# Solar_FeatherWing_02.net
KiCad netlist of a schematic drawn in EAGLE
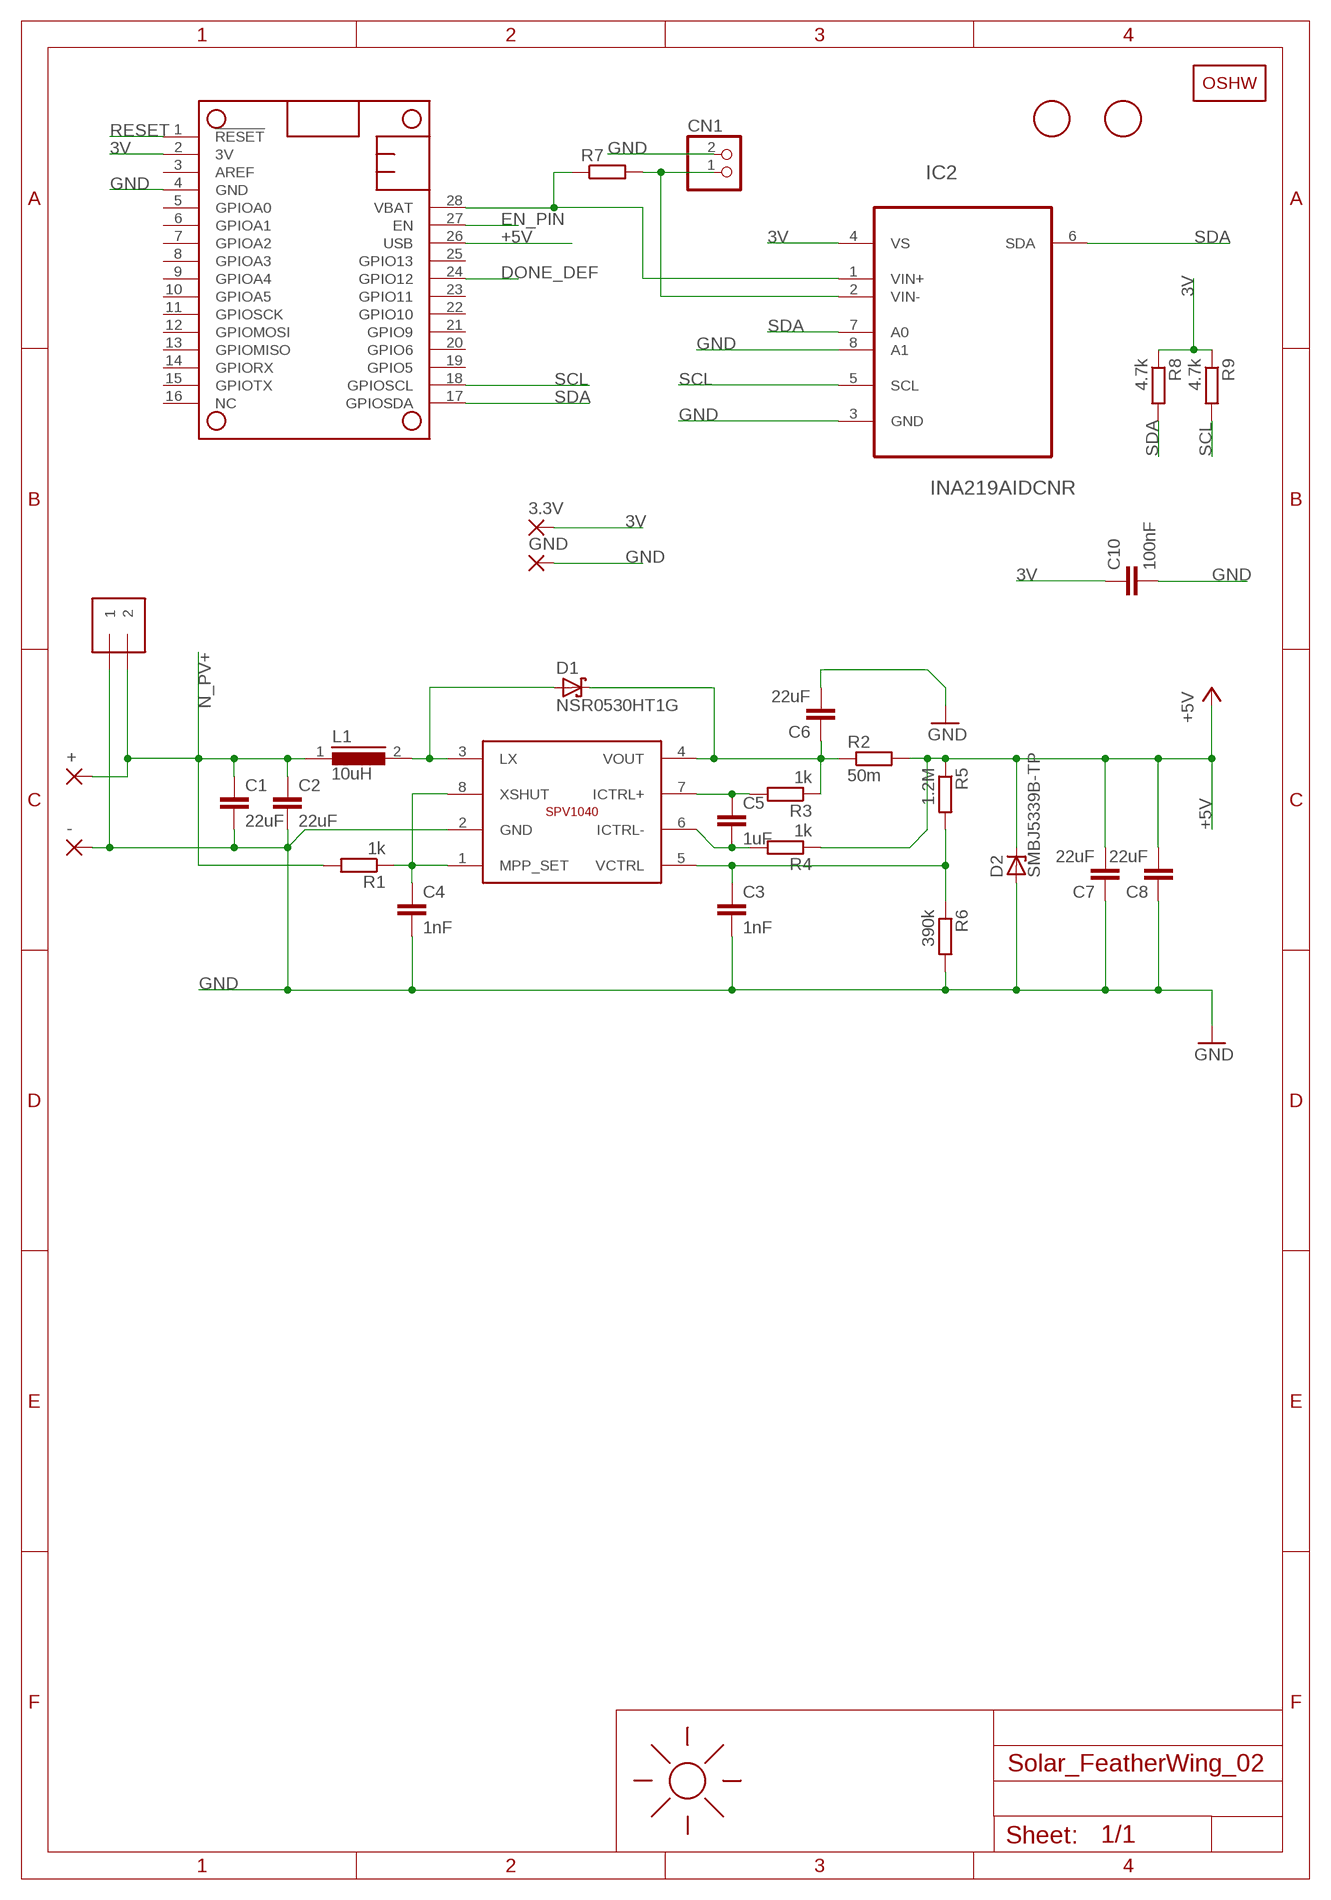
[diagram p0: schematic, sheet 1]

(export (version "E")
  (design (tool "Eeschema 10.0.6"))
  (components
    (comp (ref "+")
      (value "1,6/0,9")
      (footprint "eagle-import:1,6_0,9")
      (libsource (lib "eagle-import") (part "1,6/0,9"))
    )
    (comp (ref "-")
      (value "1,6/0,9")
      (footprint "eagle-import:1,6_0,9")
      (libsource (lib "eagle-import") (part "1,6/0,9"))
    )
    (comp (ref "3.3V")
      (value "1,6/0,9")
      (footprint "eagle-import:1,6_0,9")
      (libsource (lib "eagle-import") (part "1,6/0,9"))
    )
    (comp (ref "C1")
      (value "22uF")
      (footprint "eagle-import:C0603K")
      (libsource (lib "eagle-import") (part "C-EUC0603K"))
    )
    (comp (ref "C2")
      (value "22uF")
      (footprint "eagle-import:C0603K")
      (libsource (lib "eagle-import") (part "C-EUC0603K"))
    )
    (comp (ref "C3")
      (value "1nF")
      (footprint "eagle-import:C0603K")
      (libsource (lib "eagle-import") (part "C-EUC0603K"))
    )
    (comp (ref "C4")
      (value "1nF")
      (footprint "eagle-import:C0603K")
      (libsource (lib "eagle-import") (part "C-EUC0603K"))
    )
    (comp (ref "C5")
      (value "1uF")
      (footprint "eagle-import:C0603K")
      (libsource (lib "eagle-import") (part "C-EUC0603K"))
    )
    (comp (ref "C6")
      (value "22uF")
      (footprint "eagle-import:C0603K")
      (libsource (lib "eagle-import") (part "C-EUC0603K"))
    )
    (comp (ref "C7")
      (value "22uF")
      (footprint "eagle-import:C0603K")
      (libsource (lib "eagle-import") (part "C-EUC0603K"))
    )
    (comp (ref "C8")
      (value "22uF")
      (footprint "eagle-import:C0603K")
      (libsource (lib "eagle-import") (part "C-EUC0603K"))
    )
    (comp (ref "C10")
      (value "100nF")
      (footprint "eagle-import:C0603K")
      (libsource (lib "eagle-import") (part "C-EUC0603K"))
    )
    (comp (ref "CN1")
      (value "JST_2PIN-SMT-RA")
      (footprint "eagle-import:JST-PH-2-SMT-RA")
      (libsource (lib "eagle-import") (part "JST_2PIN-SMT-RA"))
    )
    (comp (ref "D1")
      (value "NSR0530HT1G")
      (footprint "eagle-import:SOD323_ST")
      (libsource (lib "eagle-import") (part "BAT60J"))
    )
    (comp (ref "D2")
      (value "SMBJ5339B-TP")
      (footprint "eagle-import:SMB")
      (libsource (lib "eagle-import") (part "ZENER-DIODESMB"))
    )
    (comp (ref "GND")
      (value "1,6/0,9")
      (footprint "eagle-import:1,6_0,9")
      (libsource (lib "eagle-import") (part "1,6/0,9"))
    )
    (comp (ref "IC1")
      (value "SPV1040T")
      (footprint "eagle-import:TSSOP8")
      (libsource (lib "eagle-import") (part "SPV1040T"))
    )
    (comp (ref "IC2")
      (value "INA219AIDCNR")
      (footprint "eagle-import:SOT65P280X145-8N")
      (libsource (lib "eagle-import") (part "INA219AIDCNR"))
    )
    (comp (ref "J1")
      (value "1X2-3.5MM")
      (footprint "eagle-import:1X2-3.5MM")
      (libsource (lib "eagle-import") (part "1X2-3.5MM"))
    )
    (comp (ref "L1")
      (value "10uH")
      (footprint "eagle-import:DR74")
      (libsource (lib "eagle-import") (part "DR74"))
    )
    (comp (ref "LOGO1")
      (value "OSHW_LOGOX0100")
      (footprint "eagle-import:OSHW_6X100")
      (libsource (lib "eagle-import") (part "OSHW_LOGOX0100"))
    )
    (comp (ref "MS1")
      (value "FEATHERWING")
      (footprint "eagle-import:FEATHERWING")
      (libsource (lib "eagle-import") (part "FEATHERWING"))
    )
    (comp (ref "R1")
      (value "1k")
      (footprint "eagle-import:R0603")
      (libsource (lib "eagle-import") (part "R-EU_R0603"))
    )
    (comp (ref "R2")
      (value "50m")
      (footprint "eagle-import:R0603")
      (libsource (lib "eagle-import") (part "R-EU_R0603"))
    )
    (comp (ref "R3")
      (value "1k")
      (footprint "eagle-import:R0603")
      (libsource (lib "eagle-import") (part "R-EU_R0603"))
    )
    (comp (ref "R4")
      (value "1k")
      (footprint "eagle-import:R0603")
      (libsource (lib "eagle-import") (part "R-EU_R0603"))
    )
    (comp (ref "R5")
      (value "1.2M")
      (footprint "eagle-import:R0603")
      (libsource (lib "eagle-import") (part "R-EU_R0603"))
    )
    (comp (ref "R6")
      (value "390k")
      (footprint "eagle-import:R0603")
      (libsource (lib "eagle-import") (part "R-EU_R0603"))
    )
    (comp (ref "R7")
      (value "R-EU_R1206")
      (footprint "eagle-import:R1206")
      (libsource (lib "eagle-import") (part "R-EU_R1206"))
    )
    (comp (ref "R8")
      (value "4.7k")
      (footprint "eagle-import:R0603")
      (libsource (lib "eagle-import") (part "R-EU_R0603"))
    )
    (comp (ref "R9")
      (value "4.7k")
      (footprint "eagle-import:R0603")
      (libsource (lib "eagle-import") (part "R-EU_R0603"))
    )
    (comp (ref "U$1")
      (value "SUNLOGO")
      (footprint "eagle-import:SUN")
      (libsource (lib "eagle-import") (part "SUNLOGO"))
    )
    (comp (ref "U$2")
      (value "FIDUCIAL")
      (footprint "eagle-import:FIDUCIAL_1MM")
      (libsource (lib "eagle-import") (part "FIDUCIAL"))
    )
    (comp (ref "U$3")
      (value "FIDUCIAL")
      (footprint "eagle-import:FIDUCIAL_1MM")
      (libsource (lib "eagle-import") (part "FIDUCIAL"))
    )
  )
  (nets
    (net (code "1") (name "+5V") (class "Default")
      (node (ref "C7") (pin "2") (pinfunction "2_2") (pintype "passive"))
      (node (ref "C8") (pin "2") (pinfunction "2_2") (pintype "passive"))
      (node (ref "D2") (pin "C") (pinfunction "C_C") (pintype "passive"))
      (node (ref "MS1") (pin "26") (pinfunction "USB_26") (pintype "power_in"))
      (node (ref "R2") (pin "2") (pinfunction "2_2") (pintype "passive"))
      (node (ref "R4") (pin "1") (pinfunction "1_1") (pintype "passive"))
      (node (ref "R5") (pin "1") (pinfunction "1_1") (pintype "passive"))
    )
    (net (code "2") (name "/3V") (class "Default")
      (node (ref "3.3V") (pin "1") (pinfunction "P_1") (pintype "passive"))
      (node (ref "C10") (pin "1") (pinfunction "1_1") (pintype "passive"))
      (node (ref "IC2") (pin "4") (pinfunction "VS_4") (pintype "power_in"))
      (node (ref "MS1") (pin "2") (pinfunction "3V_2") (pintype "power_in"))
      (node (ref "R8") (pin "1") (pinfunction "1_1") (pintype "passive"))
      (node (ref "R9") (pin "1") (pinfunction "1_1") (pintype "passive"))
    )
    (net (code "3") (name "/DONE_DEF") (class "Default")
      (node (ref "MS1") (pin "24") (pinfunction "GPIO12_24") (pintype "bidirectional"))
    )
    (net (code "4") (name "/EN_PIN") (class "Default")
      (node (ref "MS1") (pin "27") (pinfunction "EN_27") (pintype "passive"))
    )
    (net (code "5") (name "/N_PV+") (class "Default")
      (node (ref "+") (pin "1") (pinfunction "P_1") (pintype "passive"))
      (node (ref "C1") (pin "1") (pinfunction "1_1") (pintype "passive"))
      (node (ref "C2") (pin "1") (pinfunction "1_1") (pintype "passive"))
      (node (ref "J1") (pin "2") (pinfunction "2_2") (pintype "passive"))
      (node (ref "L1") (pin "1") (pinfunction "1_1") (pintype "passive"))
      (node (ref "R1") (pin "2") (pinfunction "2_2") (pintype "passive"))
    )
    (net (code "6") (name "/RESET") (class "Default")
      (node (ref "MS1") (pin "1") (pinfunction "~{RESET}_1") (pintype "input"))
    )
    (net (code "7") (name "/SCL") (class "Default")
      (node (ref "IC2") (pin "5") (pinfunction "SCL_5") (pintype "input"))
      (node (ref "MS1") (pin "18") (pinfunction "GPIOSCL_18") (pintype "bidirectional"))
      (node (ref "R9") (pin "2") (pinfunction "2_2") (pintype "passive"))
    )
    (net (code "8") (name "/SDA") (class "Default")
      (node (ref "IC2") (pin "6") (pinfunction "SDA_6") (pintype "bidirectional"))
      (node (ref "IC2") (pin "7") (pinfunction "A0_7") (pintype "input"))
      (node (ref "MS1") (pin "17") (pinfunction "GPIOSDA_17") (pintype "bidirectional"))
      (node (ref "R8") (pin "2") (pinfunction "2_2") (pintype "passive"))
    )
    (net (code "9") (name "GND") (class "Default")
      (node (ref "-") (pin "1") (pinfunction "P_1") (pintype "passive"))
      (node (ref "C1") (pin "2") (pinfunction "2_2") (pintype "passive"))
      (node (ref "C10") (pin "2") (pinfunction "2_2") (pintype "passive"))
      (node (ref "C2") (pin "2") (pinfunction "2_2") (pintype "passive"))
      (node (ref "C3") (pin "2") (pinfunction "2_2") (pintype "passive"))
      (node (ref "C4") (pin "2") (pinfunction "2_2") (pintype "passive"))
      (node (ref "C6") (pin "2") (pinfunction "2_2") (pintype "passive"))
      (node (ref "C7") (pin "1") (pinfunction "1_1") (pintype "passive"))
      (node (ref "C8") (pin "1") (pinfunction "1_1") (pintype "passive"))
      (node (ref "CN1") (pin "2") (pinfunction "1_2") (pintype "passive"))
      (node (ref "D2") (pin "A") (pinfunction "A_A") (pintype "passive"))
      (node (ref "GND") (pin "1") (pinfunction "P_1") (pintype "passive"))
      (node (ref "IC1") (pin "2") (pinfunction "GND_2") (pintype "power_in"))
      (node (ref "IC2") (pin "3") (pinfunction "GND_3") (pintype "passive"))
      (node (ref "IC2") (pin "8") (pinfunction "A1_8") (pintype "input"))
      (node (ref "J1") (pin "1") (pinfunction "1_1") (pintype "passive"))
      (node (ref "MS1") (pin "4") (pinfunction "GND_4") (pintype "power_in"))
      (node (ref "R6") (pin "2") (pinfunction "2_2") (pintype "passive"))
    )
    (net (code "10") (name "Net-(CN1-2)") (class "Default")
      (node (ref "CN1") (pin "1") (pinfunction "2_1") (pintype "passive"))
      (node (ref "IC2") (pin "2") (pinfunction "VIN-_2") (pintype "input"))
      (node (ref "R7") (pin "2") (pinfunction "2_2") (pintype "passive"))
    )
    (net (code "11") (name "Net-(IC1-ICTRL+)") (class "Default")
      (node (ref "C5") (pin "1") (pinfunction "1_1") (pintype "passive"))
      (node (ref "IC1") (pin "7") (pinfunction "ICTRL+_7") (pintype "input"))
      (node (ref "R3") (pin "2") (pinfunction "2_2") (pintype "passive"))
    )
    (net (code "12") (name "Net-(IC1-ICTRL-)") (class "Default")
      (node (ref "C5") (pin "2") (pinfunction "2_2") (pintype "passive"))
      (node (ref "IC1") (pin "6") (pinfunction "ICTRL-_6") (pintype "input"))
      (node (ref "R4") (pin "2") (pinfunction "2_2") (pintype "passive"))
    )
    (net (code "13") (name "Net-(IC1-LX)") (class "Default")
      (node (ref "D1") (pin "A") (pinfunction "A_A") (pintype "passive"))
      (node (ref "IC1") (pin "3") (pinfunction "LX_3") (pintype "power_in"))
      (node (ref "L1") (pin "2") (pinfunction "2_2") (pintype "passive"))
    )
    (net (code "14") (name "Net-(IC1-MPP_SET)") (class "Default")
      (node (ref "C4") (pin "1") (pinfunction "1_1") (pintype "passive"))
      (node (ref "IC1") (pin "1") (pinfunction "MPP_SET_1") (pintype "input"))
      (node (ref "IC1") (pin "8") (pinfunction "XSHUT_8") (pintype "input"))
      (node (ref "R1") (pin "1") (pinfunction "1_1") (pintype "passive"))
    )
    (net (code "15") (name "Net-(IC1-VCTRL)") (class "Default")
      (node (ref "C3") (pin "1") (pinfunction "1_1") (pintype "passive"))
      (node (ref "IC1") (pin "5") (pinfunction "VCTRL_5") (pintype "input"))
      (node (ref "R5") (pin "2") (pinfunction "2_2") (pintype "passive"))
      (node (ref "R6") (pin "1") (pinfunction "1_1") (pintype "passive"))
    )
    (net (code "16") (name "Net-(IC1-VOUT)") (class "Default")
      (node (ref "C6") (pin "1") (pinfunction "1_1") (pintype "passive"))
      (node (ref "D1") (pin "C") (pinfunction "C_C") (pintype "passive"))
      (node (ref "IC1") (pin "4") (pinfunction "VOUT_4") (pintype "power_in"))
      (node (ref "R2") (pin "1") (pinfunction "1_1") (pintype "passive"))
      (node (ref "R3") (pin "1") (pinfunction "1_1") (pintype "passive"))
    )
    (net (code "17") (name "Net-(IC2-VIN+)") (class "Default")
      (node (ref "IC2") (pin "1") (pinfunction "VIN+_1") (pintype "input"))
      (node (ref "MS1") (pin "28") (pinfunction "VBAT_28") (pintype "power_in"))
      (node (ref "R7") (pin "1") (pinfunction "1_1") (pintype "passive"))
    )
    (net (code "18") (name "unconnected-(MS1-AREF-Pad3)") (class "Default")
      (node (ref "MS1") (pin "3") (pinfunction "AREF_3") (pintype "passive"))
    )
    (net (code "19") (name "unconnected-(MS1-GPIO5-Pad19)") (class "Default")
      (node (ref "MS1") (pin "19") (pinfunction "GPIO5_19") (pintype "bidirectional"))
    )
    (net (code "20") (name "unconnected-(MS1-GPIO6-Pad20)") (class "Default")
      (node (ref "MS1") (pin "20") (pinfunction "GPIO6_20") (pintype "bidirectional"))
    )
    (net (code "21") (name "unconnected-(MS1-GPIO9-Pad21)") (class "Default")
      (node (ref "MS1") (pin "21") (pinfunction "GPIO9_21") (pintype "bidirectional"))
    )
    (net (code "22") (name "unconnected-(MS1-GPIO10-Pad22)") (class "Default")
      (node (ref "MS1") (pin "22") (pinfunction "GPIO10_22") (pintype "bidirectional"))
    )
    (net (code "23") (name "unconnected-(MS1-GPIO11-Pad23)") (class "Default")
      (node (ref "MS1") (pin "23") (pinfunction "GPIO11_23") (pintype "bidirectional"))
    )
    (net (code "24") (name "unconnected-(MS1-GPIO13-Pad25)") (class "Default")
      (node (ref "MS1") (pin "25") (pinfunction "GPIO13_25") (pintype "bidirectional"))
    )
    (net (code "25") (name "unconnected-(MS1-GPIOA0-Pad5)") (class "Default")
      (node (ref "MS1") (pin "5") (pinfunction "GPIOA0_5") (pintype "bidirectional"))
    )
    (net (code "26") (name "unconnected-(MS1-GPIOA1-Pad6)") (class "Default")
      (node (ref "MS1") (pin "6") (pinfunction "GPIOA1_6") (pintype "bidirectional"))
    )
    (net (code "27") (name "unconnected-(MS1-GPIOA2-Pad7)") (class "Default")
      (node (ref "MS1") (pin "7") (pinfunction "GPIOA2_7") (pintype "bidirectional"))
    )
    (net (code "28") (name "unconnected-(MS1-GPIOA3-Pad8)") (class "Default")
      (node (ref "MS1") (pin "8") (pinfunction "GPIOA3_8") (pintype "bidirectional"))
    )
    (net (code "29") (name "unconnected-(MS1-GPIOA4-Pad9)") (class "Default")
      (node (ref "MS1") (pin "9") (pinfunction "GPIOA4_9") (pintype "bidirectional"))
    )
    (net (code "30") (name "unconnected-(MS1-GPIOA5-Pad10)") (class "Default")
      (node (ref "MS1") (pin "10") (pinfunction "GPIOA5_10") (pintype "bidirectional"))
    )
    (net (code "31") (name "unconnected-(MS1-GPIOMISO-Pad13)") (class "Default")
      (node (ref "MS1") (pin "13") (pinfunction "GPIOMISO_13") (pintype "bidirectional"))
    )
    (net (code "32") (name "unconnected-(MS1-GPIOMOSI-Pad12)") (class "Default")
      (node (ref "MS1") (pin "12") (pinfunction "GPIOMOSI_12") (pintype "bidirectional"))
    )
    (net (code "33") (name "unconnected-(MS1-GPIORX-Pad14)") (class "Default")
      (node (ref "MS1") (pin "14") (pinfunction "GPIORX_14") (pintype "bidirectional"))
    )
    (net (code "34") (name "unconnected-(MS1-GPIOSCK-Pad11)") (class "Default")
      (node (ref "MS1") (pin "11") (pinfunction "GPIOSCK_11") (pintype "bidirectional"))
    )
    (net (code "35") (name "unconnected-(MS1-GPIOTX-Pad15)") (class "Default")
      (node (ref "MS1") (pin "15") (pinfunction "GPIOTX_15") (pintype "bidirectional"))
    )
    (net (code "36") (name "unconnected-(MS1-NC-Pad16)") (class "Default")
      (node (ref "MS1") (pin "16") (pinfunction "NC_16") (pintype "passive"))
    )
  )
)
